# SCH_ESP32-LSHT-M-H-Project-Folder_2024-0.net
KiCad netlist of a schematic drawn in EasyEDA
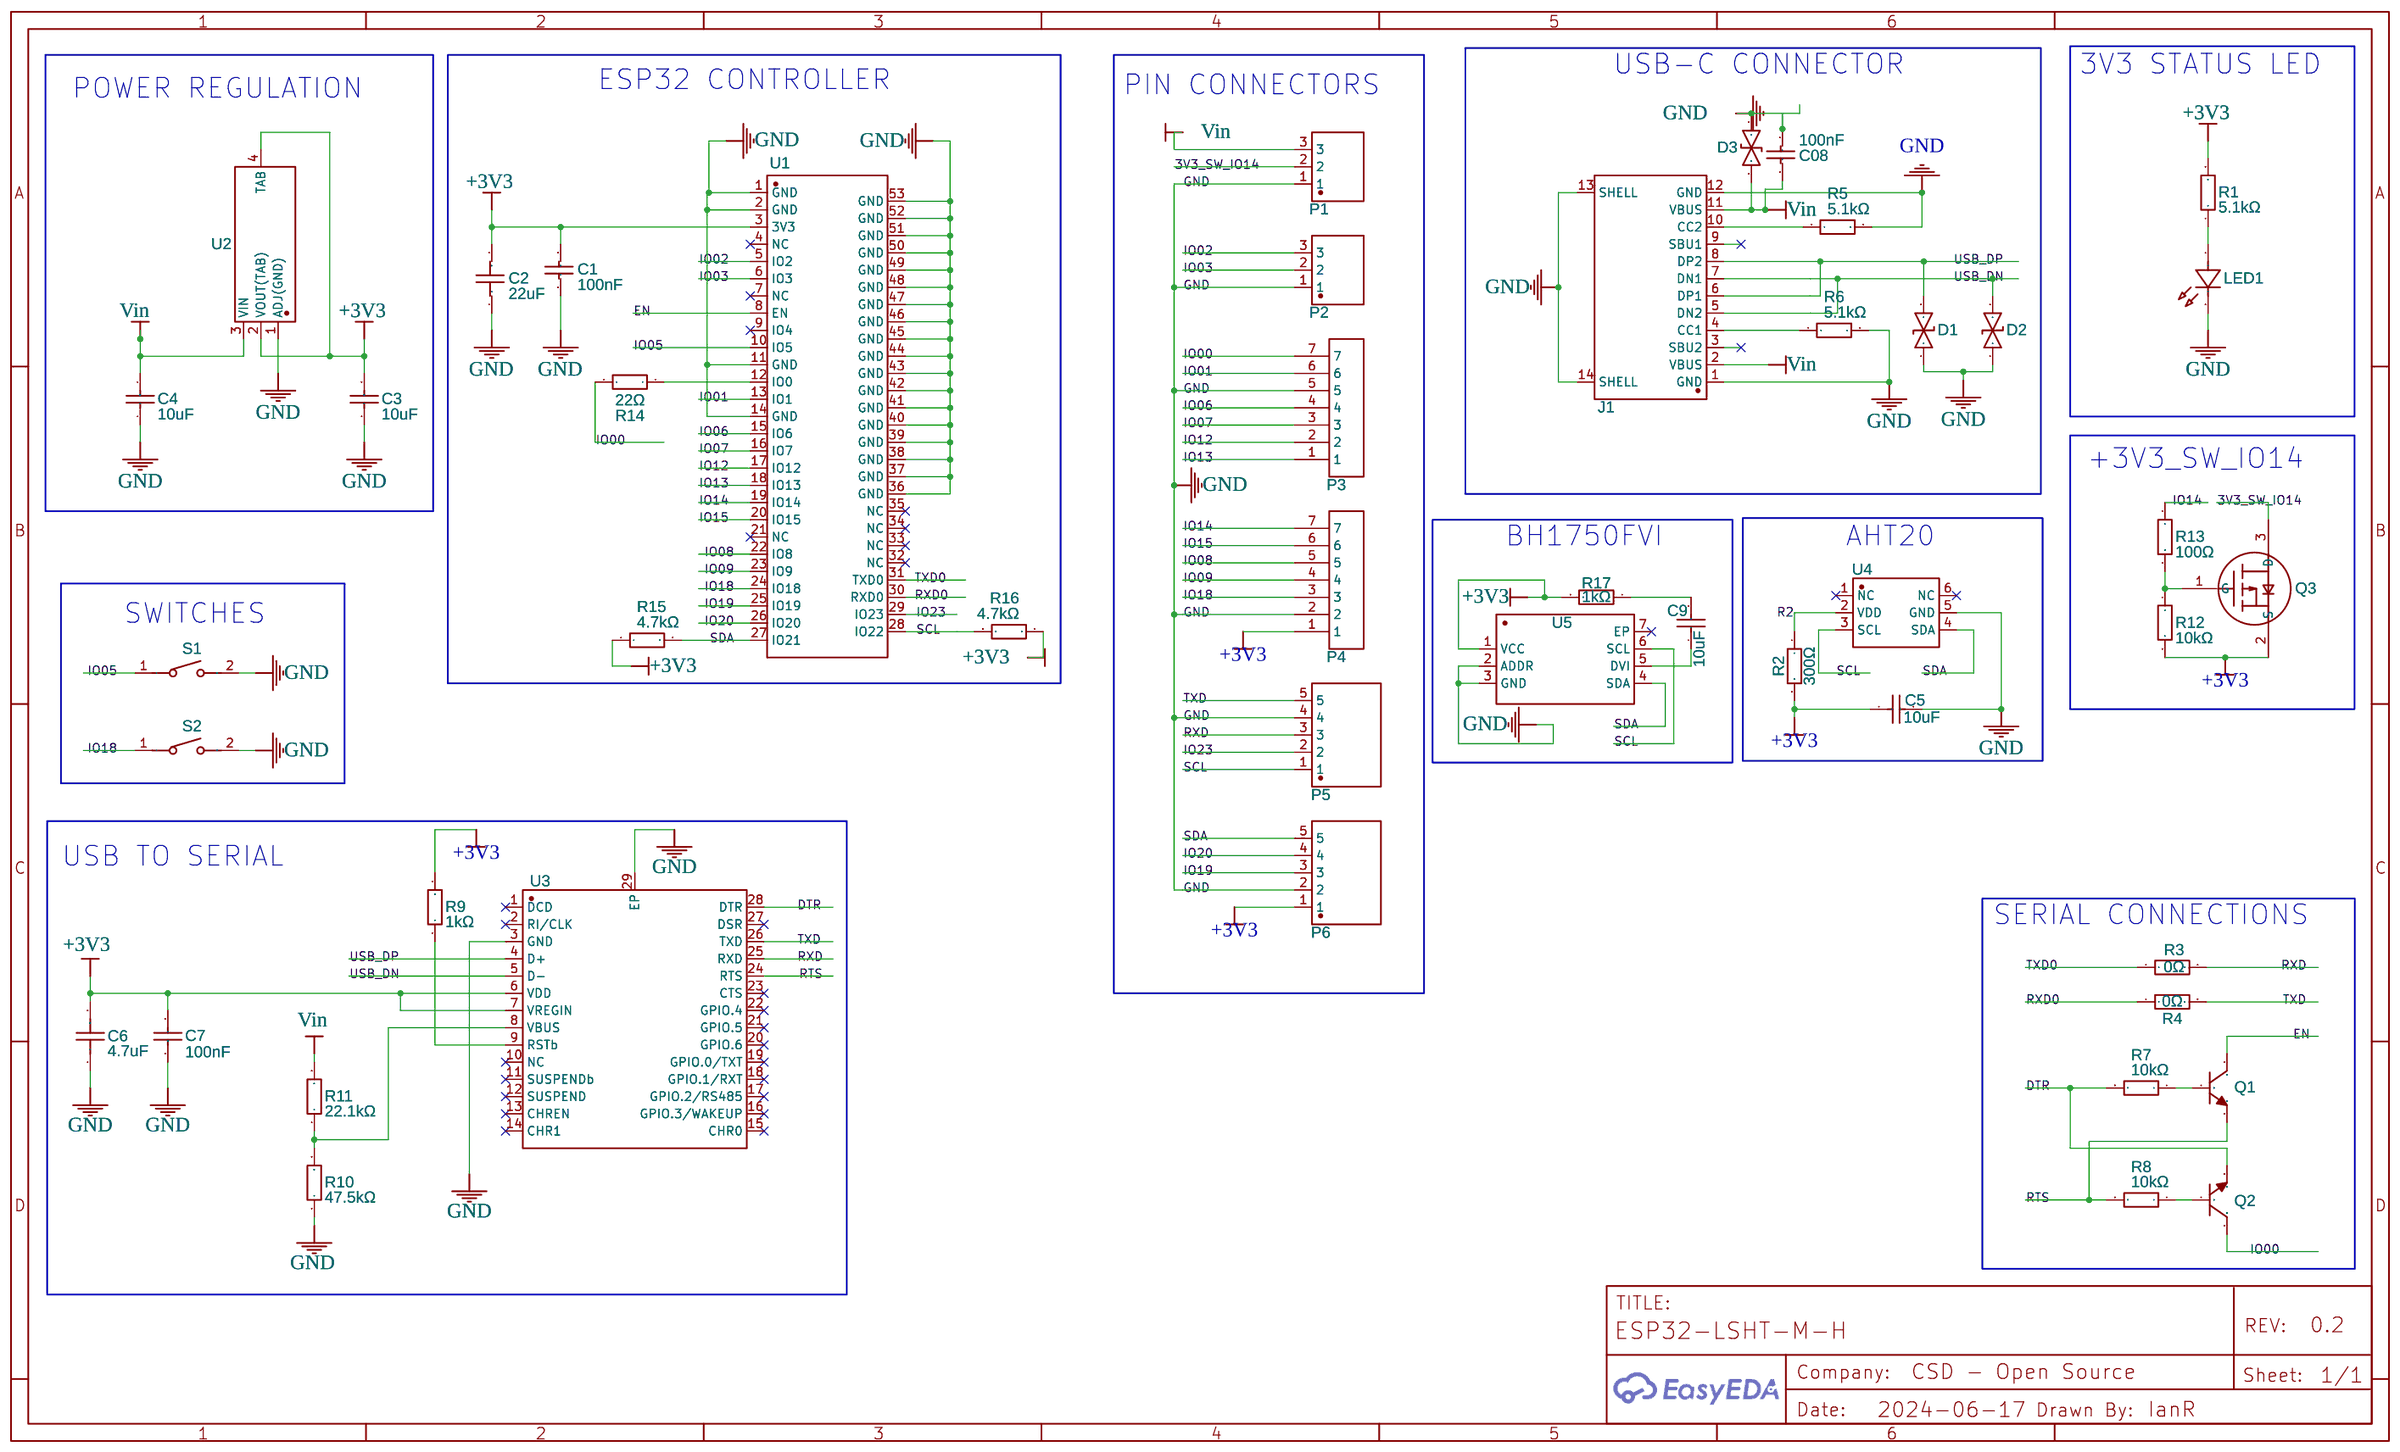
[diagram p0: schematic sheet]

(export (version "E")
  (design (tool "Eeschema 10.0.6"))
  (components
    (comp (ref "C1")
      (value "100nF")
      (fields
        (field (name "Manufacturer Part") "CL05B104KO5NNNC")
        (field (name "Manufacturer") "SAMSUNG(三星)")
      )
      (libsource (lib "") (part "CL05B104KO5NNNC"))
    )
    (comp (ref "C2")
      (value "22uF")
      (fields
        (field (name "Manufacturer Part") "GRM158R61A226ME15D")
        (field (name "Manufacturer") "muRata(村田)")
      )
      (libsource (lib "") (part "GRM158R61A226ME15D"))
    )
    (comp (ref "C3")
      (value "10uF")
      (fields
        (field (name "Manufacturer Part") "CL05A106MQ5NUNC")
        (field (name "Manufacturer") "SAMSUNG(三星)")
      )
      (libsource (lib "") (part "CL05A106MQ5NUNC_1"))
    )
    (comp (ref "C4")
      (value "10uF")
      (fields
        (field (name "Manufacturer Part") "CL05A106MQ5NUNC")
        (field (name "Manufacturer") "SAMSUNG(三星)")
      )
      (libsource (lib "") (part "CL05A106MQ5NUNC_1"))
    )
    (comp (ref "C5")
      (value "10uF")
      (fields
        (field (name "Manufacturer Part") "CL05A106MQ5NUNC")
        (field (name "Manufacturer") "SAMSUNG(三星)")
      )
      (libsource (lib "") (part "CL05A106MQ5NUNC"))
    )
    (comp (ref "C6")
      (value "4.7uF")
      (fields
        (field (name "Manufacturer Part") "CL05A475KP5NRNC")
        (field (name "Manufacturer") "SAMSUNG(三星)")
      )
      (libsource (lib "") (part "CL05A475KP5NRNC"))
    )
    (comp (ref "C7")
      (value "100nF")
      (fields
        (field (name "Manufacturer Part") "CL05B104KO5NNNC")
        (field (name "Manufacturer") "SAMSUNG(三星)")
      )
      (libsource (lib "") (part "CL05B104KO5NNNC_2"))
    )
    (comp (ref "C08")
      (value "100nF")
      (fields
        (field (name "Manufacturer Part") "CL05B104KO5NNNC")
        (field (name "Manufacturer") "SAMSUNG(三星)")
      )
      (libsource (lib "") (part "CL05B104KO5NNNC_1"))
    )
    (comp (ref "C9")
      (value "10uF")
      (fields
        (field (name "Manufacturer Part") "CL05A106MQ5NUNC")
        (field (name "Manufacturer") "SAMSUNG(三星)")
      )
      (libsource (lib "") (part "CL05A106MQ5NUNC_1"))
    )
    (comp (ref "D1")
      (value "LESD5D5.0CT1G_C5246195")
      (fields
        (field (name "Manufacturer Part") "LESD5D5.0CT1G")
        (field (name "Manufacturer") "Leiditech(雷卯电子)")
      )
      (libsource (lib "") (part "LESD5D5.0CT1G_C5246195_1"))
    )
    (comp (ref "D2")
      (value "LESD5D5.0CT1G_C5246195")
      (fields
        (field (name "Manufacturer Part") "LESD5D5.0CT1G")
        (field (name "Manufacturer") "Leiditech(雷卯电子)")
      )
      (libsource (lib "") (part "LESD5D5.0CT1G_C5246195_1"))
    )
    (comp (ref "D3")
      (value "LESD5D5.0CT1G_C5246195")
      (fields
        (field (name "Manufacturer Part") "LESD5D5.0CT1G")
        (field (name "Manufacturer") "Leiditech(雷卯电子)")
      )
      (libsource (lib "") (part "LESD5D5.0CT1G_C5246195"))
    )
    (comp (ref "J1")
      (value "TYPE-C 16PIN 2MD(073)")
      (fields (field (name "Manufacturer") "SHOU HAN(首韩)"))
      (libsource (lib "") (part "TYPE-C 16PIN 2MD(073)"))
    )
    (comp (ref "LED1")
      (value "XL-1005SURC")
      (fields (field (name "Manufacturer") "XINGLIGHT(成兴光)"))
      (libsource (lib "") (part "XL-1005SURC"))
    )
    (comp (ref "P1")
      (value "B3B-ZR-(LF)(SN)")
      (fields (field (name "Manufacturer Part") "B3B-ZR(LF)(SN)") (field (name "Manufacturer") "JST"))
      (libsource (lib "") (part "B3B-ZR-(LF)(SN)"))
    )
    (comp (ref "P2")
      (value "B3B-ZR-(LF)(SN)")
      (fields (field (name "Manufacturer Part") "B3B-ZR(LF)(SN)") (field (name "Manufacturer") "JST"))
      (libsource (lib "") (part "B3B-ZR-(LF)(SN)"))
    )
    (comp (ref "P3")
      (value "B7B-ZR (LF)(SN)")
      (fields (field (name "Manufacturer Part") "B7B-ZR(LF)(SN)") (field (name "Manufacturer") "JST"))
      (libsource (lib "") (part "B7B-ZR (LF)(SN)"))
    )
    (comp (ref "P4")
      (value "B7B-ZR (LF)(SN)")
      (fields (field (name "Manufacturer Part") "B7B-ZR(LF)(SN)") (field (name "Manufacturer") "JST"))
      (libsource (lib "") (part "B7B-ZR (LF)(SN)"))
    )
    (comp (ref "P5")
      (value "B5B-ZR-(LF)(SN)")
      (fields (field (name "Manufacturer Part") "B5B-ZR(LF)(SN)") (field (name "Manufacturer") "JST"))
      (libsource (lib "") (part "B5B-ZR-(LF)(SN)"))
    )
    (comp (ref "P6")
      (value "B5B-ZR-(LF)(SN)")
      (fields (field (name "Manufacturer Part") "B5B-ZR(LF)(SN)") (field (name "Manufacturer") "JST"))
      (libsource (lib "") (part "B5B-ZR-(LF)(SN)"))
    )
    (comp (ref "Q1")
      (value "SS8050-G")
      (fields (field (name "Manufacturer") "CJ(江苏长电/长晶)"))
      (libsource (lib "") (part "SS8050-G_1"))
    )
    (comp (ref "Q2")
      (value "SS8050-G")
      (fields (field (name "Manufacturer") "CJ(江苏长电/长晶)"))
      (libsource (lib "") (part "SS8050-G"))
    )
    (comp (ref "Q3")
      (value "SI2333DS-T1-E3")
      (fields (field (name "Manufacturer") "VISHAY(威世)"))
      (libsource (lib "") (part "SI2333DS-T1-E3"))
    )
    (comp (ref "R1")
      (value "5.1kΩ")
      (fields
        (field (name "Manufacturer Part") "0402WGF5101TCE")
        (field (name "Manufacturer") "UNI-ROYAL(厚声)")
      )
      (libsource (lib "") (part "0402WGF5101TCE_1"))
    )
    (comp (ref "R2")
      (value "300Ω")
      (fields (field (name "Manufacturer Part") "RC0402FR-07300RL") (field (name "Manufacturer") "YAGEO(国巨)"))
      (libsource (lib "") (part "RC0402FR-07300RL"))
    )
    (comp (ref "R3")
      (value "0Ω")
      (fields
        (field (name "Manufacturer Part") "0402WGF0000TCE")
        (field (name "Manufacturer") "UNI-ROYAL(厚声)")
      )
      (libsource (lib "") (part "0402WGF0000TCE"))
    )
    (comp (ref "R4")
      (value "0Ω")
      (fields
        (field (name "Manufacturer Part") "0402WGF0000TCE")
        (field (name "Manufacturer") "UNI-ROYAL(厚声)")
      )
      (libsource (lib "") (part "0402WGF0000TCE"))
    )
    (comp (ref "R5")
      (value "5.1kΩ")
      (fields
        (field (name "Manufacturer Part") "0402WGF5101TCE")
        (field (name "Manufacturer") "UNI-ROYAL(厚声)")
      )
      (libsource (lib "") (part "0402WGF5101TCE"))
    )
    (comp (ref "R6")
      (value "5.1kΩ")
      (fields
        (field (name "Manufacturer Part") "0402WGF5101TCE")
        (field (name "Manufacturer") "UNI-ROYAL(厚声)")
      )
      (libsource (lib "") (part "0402WGF5101TCE"))
    )
    (comp (ref "R7")
      (value "10kΩ")
      (fields
        (field (name "Manufacturer Part") "0402WGF1002TCE")
        (field (name "Manufacturer") "UNI-ROYAL(厚声)")
      )
      (libsource (lib "") (part "0402WGF1002TCE"))
    )
    (comp (ref "R8")
      (value "10kΩ")
      (fields
        (field (name "Manufacturer Part") "0402WGF1002TCE")
        (field (name "Manufacturer") "UNI-ROYAL(厚声)")
      )
      (libsource (lib "") (part "0402WGF1002TCE"))
    )
    (comp (ref "R9")
      (value "1kΩ")
      (fields
        (field (name "Manufacturer Part") "0402WGF1001TCE")
        (field (name "Manufacturer") "UNI-ROYAL(厚声)")
      )
      (libsource (lib "") (part "0402WGF1001TCE_1"))
    )
    (comp (ref "R10")
      (value "47.5kΩ")
      (fields
        (field (name "Manufacturer Part") "0402WGF4752TCE")
        (field (name "Manufacturer") "UNI-ROYAL(厚声)")
      )
      (libsource (lib "") (part "0402WGF4752TCE"))
    )
    (comp (ref "R11")
      (value "22.1kΩ")
      (fields
        (field (name "Manufacturer Part") "0402WGF2212TCE")
        (field (name "Manufacturer") "UNI-ROYAL(厚声)")
      )
      (libsource (lib "") (part "0402WGF2212TCE"))
    )
    (comp (ref "R12")
      (value "10kΩ")
      (fields
        (field (name "Manufacturer Part") "0402WGF1002TCE")
        (field (name "Manufacturer") "UNI-ROYAL(厚声)")
      )
      (libsource (lib "") (part "0402WGF1002TCE_1"))
    )
    (comp (ref "R13")
      (value "100Ω")
      (fields (field (name "Manufacturer Part") "RC0402FR-07100RL") (field (name "Manufacturer") "YAGEO(国巨)"))
      (libsource (lib "") (part "RC0402FR-07100RL"))
    )
    (comp (ref "R14")
      (value "22Ω")
      (fields
        (field (name "Manufacturer Part") "0402WGF220JTCE")
        (field (name "Manufacturer") "UNI-ROYAL(厚声)")
      )
      (libsource (lib "") (part "0402WGF220JTCE"))
    )
    (comp (ref "R15")
      (value "4.7kΩ")
      (fields
        (field (name "Manufacturer Part") "0402WGF4701TCE")
        (field (name "Manufacturer") "UNI-ROYAL(厚声)")
      )
      (libsource (lib "") (part "0402WGF4701TCE_1"))
    )
    (comp (ref "R16")
      (value "4.7kΩ")
      (fields
        (field (name "Manufacturer Part") "0402WGF4701TCE")
        (field (name "Manufacturer") "UNI-ROYAL(厚声)")
      )
      (libsource (lib "") (part "0402WGF4701TCE"))
    )
    (comp (ref "R17")
      (value "1kΩ")
      (fields
        (field (name "Manufacturer Part") "0402WGF1001TCE")
        (field (name "Manufacturer") "UNI-ROYAL(厚声)")
      )
      (libsource (lib "") (part "0402WGF1001TCE"))
    )
    (comp (ref "S1")
      (value "TS-1088-AR02016")
      (fields (field (name "Manufacturer") "XUNPU(讯普)"))
      (libsource (lib "") (part "TS-1088-AR02016"))
    )
    (comp (ref "S2")
      (value "TS-1088-AR02016")
      (fields (field (name "Manufacturer") "XUNPU(讯普)"))
      (libsource (lib "") (part "TS-1088-AR02016"))
    )
    (comp (ref "U1")
      (value "ESP32-C6-MINI-1-N4")
      (fields (field (name "Manufacturer") "ESPRESSIF(乐鑫)"))
      (libsource (lib "") (part "ESP32-C6-MINI-1-N4"))
    )
    (comp (ref "U2")
      (value "AMS1117-3.3_C347222")
      (fields (field (name "Manufacturer Part") "AMS1117-3.3") (field (name "Manufacturer") "UMW(友台半导体)"))
      (libsource (lib "") (part "AMS1117-3.3_C347222"))
    )
    (comp (ref "U3")
      (value "CP2102N-A02-GQFN28R")
      (fields (field (name "Manufacturer") "SKYWORKS/SILICON LABS(芯科)"))
      (libsource (lib "") (part "CP2102N-A02-GQFN28R"))
    )
    (comp (ref "U4")
      (value "AHT20_C2757850")
      (fields (field (name "Manufacturer Part") "AHT20") (field (name "Manufacturer") "广州奥松"))
      (libsource (lib "") (part "AHT20_C2757850"))
    )
    (comp (ref "U5")
      (value "BH1750FVI-TR")
      (fields (field (name "Manufacturer") "ROHM(罗姆)"))
      (libsource (lib "") (part "BH1750FVI-TR"))
    )
  )
  (nets
    (net (code "1") (name "+3V3") (class "Default")
      (node (ref "C1") (pin "2") (pinfunction "2_2") (pintype "input"))
      (node (ref "C2") (pin "2") (pinfunction "2_2") (pintype "unspecified"))
      (node (ref "C3") (pin "2") (pinfunction "2_2") (pintype "input"))
      (node (ref "C5") (pin "1") (pinfunction "1_1") (pintype "input"))
      (node (ref "C6") (pin "2") (pinfunction "2_2") (pintype "unspecified"))
      (node (ref "C7") (pin "2") (pinfunction "2_2") (pintype "input"))
      (node (ref "P4") (pin "1") (pinfunction "1_1") (pintype "unspecified"))
      (node (ref "P6") (pin "1") (pinfunction "1_1") (pintype "unspecified"))
      (node (ref "Q3") (pin "2") (pinfunction "S_2") (pintype "unspecified"))
      (node (ref "R1") (pin "2") (pinfunction "2_2") (pintype "input"))
      (node (ref "R12") (pin "2") (pinfunction "2_2") (pintype "input"))
      (node (ref "R15") (pin "1") (pinfunction "1_1") (pintype "input"))
      (node (ref "R16") (pin "1") (pinfunction "1_1") (pintype "input"))
      (node (ref "R17") (pin "2") (pinfunction "2_2") (pintype "input"))
      (node (ref "R2") (pin "2") (pinfunction "2_2") (pintype "input"))
      (node (ref "R9") (pin "2") (pinfunction "2_2") (pintype "input"))
      (node (ref "U1") (pin "3") (pinfunction "3V3_3") (pintype "unspecified"))
      (node (ref "U2") (pin "2") (pinfunction "VOUT(TAB)_2") (pintype "unspecified"))
      (node (ref "U2") (pin "4") (pinfunction "TAB_4") (pintype "unspecified"))
      (node (ref "U3") (pin "6") (pinfunction "VDD_6") (pintype "unspecified"))
      (node (ref "U3") (pin "7") (pinfunction "VREGIN_7") (pintype "unspecified"))
      (node (ref "U5") (pin "1") (pinfunction "VCC_1") (pintype "unspecified"))
    )
    (net (code "2") (name "/3V3_SW_IO14") (class "Default")
      (node (ref "P1") (pin "2") (pinfunction "2_2") (pintype "unspecified"))
      (node (ref "Q3") (pin "3") (pinfunction "D_3") (pintype "unspecified"))
    )
    (net (code "3") (name "/DTR") (class "Default")
      (node (ref "Q2") (pin "2") (pinfunction "E_2") (pintype "input"))
      (node (ref "R7") (pin "2") (pinfunction "2_2") (pintype "input"))
      (node (ref "U3") (pin "28") (pinfunction "DTR_28") (pintype "unspecified"))
    )
    (net (code "4") (name "/EN") (class "Default")
      (node (ref "Q1") (pin "3") (pinfunction "C_3") (pintype "input"))
      (node (ref "U1") (pin "8") (pinfunction "EN_8") (pintype "unspecified"))
    )
    (net (code "5") (name "/IO00") (class "Default")
      (node (ref "P3") (pin "7") (pinfunction "7_7") (pintype "unspecified"))
      (node (ref "Q2") (pin "3") (pinfunction "C_3") (pintype "input"))
      (node (ref "R14") (pin "2") (pinfunction "2_2") (pintype "input"))
    )
    (net (code "6") (name "/IO01") (class "Default")
      (node (ref "P3") (pin "6") (pinfunction "6_6") (pintype "unspecified"))
      (node (ref "U1") (pin "13") (pinfunction "IO1_13") (pintype "unspecified"))
    )
    (net (code "7") (name "/IO02") (class "Default")
      (node (ref "P2") (pin "3") (pinfunction "3_3") (pintype "unspecified"))
      (node (ref "U1") (pin "5") (pinfunction "IO2_5") (pintype "unspecified"))
    )
    (net (code "8") (name "/IO03") (class "Default")
      (node (ref "P2") (pin "2") (pinfunction "2_2") (pintype "unspecified"))
      (node (ref "U1") (pin "6") (pinfunction "IO3_6") (pintype "unspecified"))
    )
    (net (code "9") (name "/IO05") (class "Default")
      (node (ref "S1") (pin "1") (pinfunction "1_1") (pintype "unspecified"))
      (node (ref "U1") (pin "10") (pinfunction "IO5_10") (pintype "unspecified"))
    )
    (net (code "10") (name "/IO06") (class "Default")
      (node (ref "P3") (pin "4") (pinfunction "4_4") (pintype "unspecified"))
      (node (ref "U1") (pin "15") (pinfunction "IO6_15") (pintype "unspecified"))
    )
    (net (code "11") (name "/IO07") (class "Default")
      (node (ref "P3") (pin "3") (pinfunction "3_3") (pintype "unspecified"))
      (node (ref "U1") (pin "16") (pinfunction "IO7_16") (pintype "unspecified"))
    )
    (net (code "12") (name "/IO08") (class "Default")
      (node (ref "P4") (pin "5") (pinfunction "5_5") (pintype "unspecified"))
      (node (ref "U1") (pin "22") (pinfunction "IO8_22") (pintype "unspecified"))
    )
    (net (code "13") (name "/IO09") (class "Default")
      (node (ref "P4") (pin "4") (pinfunction "4_4") (pintype "unspecified"))
      (node (ref "U1") (pin "23") (pinfunction "IO9_23") (pintype "unspecified"))
    )
    (net (code "14") (name "/IO12") (class "Default")
      (node (ref "P3") (pin "2") (pinfunction "2_2") (pintype "unspecified"))
      (node (ref "U1") (pin "17") (pinfunction "IO12_17") (pintype "unspecified"))
    )
    (net (code "15") (name "/IO13") (class "Default")
      (node (ref "P3") (pin "1") (pinfunction "1_1") (pintype "unspecified"))
      (node (ref "U1") (pin "18") (pinfunction "IO13_18") (pintype "unspecified"))
    )
    (net (code "16") (name "/IO14") (class "Default")
      (node (ref "P4") (pin "7") (pinfunction "7_7") (pintype "unspecified"))
      (node (ref "R13") (pin "1") (pinfunction "1_1") (pintype "input"))
      (node (ref "U1") (pin "19") (pinfunction "IO14_19") (pintype "unspecified"))
    )
    (net (code "17") (name "/IO15") (class "Default")
      (node (ref "P4") (pin "6") (pinfunction "6_6") (pintype "unspecified"))
      (node (ref "U1") (pin "20") (pinfunction "IO15_20") (pintype "unspecified"))
    )
    (net (code "18") (name "/IO18") (class "Default")
      (node (ref "P4") (pin "3") (pinfunction "3_3") (pintype "unspecified"))
      (node (ref "S2") (pin "1") (pinfunction "1_1") (pintype "unspecified"))
      (node (ref "U1") (pin "24") (pinfunction "IO18_24") (pintype "unspecified"))
    )
    (net (code "19") (name "/IO19") (class "Default")
      (node (ref "P6") (pin "3") (pinfunction "3_3") (pintype "unspecified"))
      (node (ref "U1") (pin "25") (pinfunction "IO19_25") (pintype "unspecified"))
    )
    (net (code "20") (name "/IO20") (class "Default")
      (node (ref "P6") (pin "4") (pinfunction "4_4") (pintype "unspecified"))
      (node (ref "U1") (pin "26") (pinfunction "IO20_26") (pintype "unspecified"))
    )
    (net (code "21") (name "/IO23") (class "Default")
      (node (ref "P5") (pin "2") (pinfunction "2_2") (pintype "unspecified"))
      (node (ref "U1") (pin "29") (pinfunction "IO23_29") (pintype "unspecified"))
    )
    (net (code "22") (name "/R2") (class "Default")
      (node (ref "R2") (pin "1") (pinfunction "1_1") (pintype "input"))
      (node (ref "U4") (pin "2") (pinfunction "VDD_2") (pintype "unspecified"))
    )
    (net (code "23") (name "/RTS") (class "Default")
      (node (ref "Q1") (pin "2") (pinfunction "E_2") (pintype "input"))
      (node (ref "R8") (pin "2") (pinfunction "2_2") (pintype "input"))
      (node (ref "U3") (pin "24") (pinfunction "RTS_24") (pintype "unspecified"))
    )
    (net (code "24") (name "/RXD") (class "Default")
      (node (ref "P5") (pin "3") (pinfunction "3_3") (pintype "unspecified"))
      (node (ref "R3") (pin "2") (pinfunction "2_2") (pintype "input"))
      (node (ref "U3") (pin "25") (pinfunction "RXD_25") (pintype "unspecified"))
    )
    (net (code "25") (name "/RXD0") (class "Default")
      (node (ref "R4") (pin "1") (pinfunction "1_1") (pintype "input"))
      (node (ref "U1") (pin "30") (pinfunction "RXD0_30") (pintype "unspecified"))
    )
    (net (code "26") (name "/SCL") (class "Default")
      (node (ref "P5") (pin "1") (pinfunction "1_1") (pintype "unspecified"))
      (node (ref "R16") (pin "2") (pinfunction "2_2") (pintype "input"))
      (node (ref "U1") (pin "28") (pinfunction "IO22_28") (pintype "unspecified"))
      (node (ref "U4") (pin "3") (pinfunction "SCL_3") (pintype "unspecified"))
      (node (ref "U5") (pin "6") (pinfunction "SCL_6") (pintype "unspecified"))
    )
    (net (code "27") (name "/SDA") (class "Default")
      (node (ref "P6") (pin "5") (pinfunction "5_5") (pintype "unspecified"))
      (node (ref "R15") (pin "2") (pinfunction "2_2") (pintype "input"))
      (node (ref "U1") (pin "27") (pinfunction "IO21_27") (pintype "unspecified"))
      (node (ref "U4") (pin "4") (pinfunction "SDA_4") (pintype "unspecified"))
      (node (ref "U5") (pin "4") (pinfunction "SDA_4") (pintype "unspecified"))
    )
    (net (code "28") (name "/TXD") (class "Default")
      (node (ref "P5") (pin "5") (pinfunction "5_5") (pintype "unspecified"))
      (node (ref "R4") (pin "2") (pinfunction "2_2") (pintype "input"))
      (node (ref "U3") (pin "26") (pinfunction "TXD_26") (pintype "unspecified"))
    )
    (net (code "29") (name "/TXD0") (class "Default")
      (node (ref "R3") (pin "1") (pinfunction "1_1") (pintype "input"))
      (node (ref "U1") (pin "31") (pinfunction "TXD0_31") (pintype "unspecified"))
    )
    (net (code "30") (name "/USB_DN") (class "Default")
      (node (ref "D2") (pin "2") (pinfunction "2_2") (pintype "unspecified"))
      (node (ref "J1") (pin "5") (pinfunction "DN2_5") (pintype "unspecified"))
      (node (ref "J1") (pin "7") (pinfunction "DN1_7") (pintype "unspecified"))
      (node (ref "U3") (pin "5") (pinfunction "D-_5") (pintype "unspecified"))
    )
    (net (code "31") (name "/USB_DP") (class "Default")
      (node (ref "D1") (pin "2") (pinfunction "2_2") (pintype "unspecified"))
      (node (ref "J1") (pin "6") (pinfunction "DP1_6") (pintype "unspecified"))
      (node (ref "J1") (pin "8") (pinfunction "DP2_8") (pintype "unspecified"))
      (node (ref "U3") (pin "4") (pinfunction "D+_4") (pintype "unspecified"))
    )
    (net (code "32") (name "GND") (class "Default")
      (node (ref "C08") (pin "1") (pinfunction "1_1") (pintype "input"))
      (node (ref "C1") (pin "1") (pinfunction "1_1") (pintype "input"))
      (node (ref "C2") (pin "1") (pinfunction "1_1") (pintype "unspecified"))
      (node (ref "C3") (pin "1") (pinfunction "1_1") (pintype "input"))
      (node (ref "C4") (pin "1") (pinfunction "1_1") (pintype "input"))
      (node (ref "C5") (pin "2") (pinfunction "2_2") (pintype "input"))
      (node (ref "C6") (pin "1") (pinfunction "1_1") (pintype "unspecified"))
      (node (ref "C7") (pin "1") (pinfunction "1_1") (pintype "input"))
      (node (ref "D1") (pin "1") (pinfunction "1_1") (pintype "unspecified"))
      (node (ref "D2") (pin "1") (pinfunction "1_1") (pintype "unspecified"))
      (node (ref "D3") (pin "1") (pinfunction "1_1") (pintype "unspecified"))
      (node (ref "J1") (pin "1") (pinfunction "GND_1") (pintype "unspecified"))
      (node (ref "J1") (pin "12") (pinfunction "GND_12") (pintype "unspecified"))
      (node (ref "J1") (pin "13") (pinfunction "SHELL_13") (pintype "unspecified"))
      (node (ref "J1") (pin "14") (pinfunction "SHELL_14") (pintype "unspecified"))
      (node (ref "LED1") (pin "2") (pinfunction "A_2") (pintype "unspecified"))
      (node (ref "P1") (pin "1") (pinfunction "1_1") (pintype "unspecified"))
      (node (ref "P2") (pin "1") (pinfunction "1_1") (pintype "unspecified"))
      (node (ref "P3") (pin "5") (pinfunction "5_5") (pintype "unspecified"))
      (node (ref "P4") (pin "2") (pinfunction "2_2") (pintype "unspecified"))
      (node (ref "P5") (pin "4") (pinfunction "4_4") (pintype "unspecified"))
      (node (ref "P6") (pin "2") (pinfunction "2_2") (pintype "unspecified"))
      (node (ref "R10") (pin "1") (pinfunction "1_1") (pintype "input"))
      (node (ref "R5") (pin "2") (pinfunction "2_2") (pintype "input"))
      (node (ref "R6") (pin "2") (pinfunction "2_2") (pintype "input"))
      (node (ref "S1") (pin "2") (pinfunction "2_2") (pintype "unspecified"))
      (node (ref "S2") (pin "2") (pinfunction "2_2") (pintype "unspecified"))
      (node (ref "U1") (pin "1") (pinfunction "GND_1") (pintype "unspecified"))
      (node (ref "U1") (pin "11") (pinfunction "GND_11") (pintype "unspecified"))
      (node (ref "U1") (pin "14") (pinfunction "GND_14") (pintype "unspecified"))
      (node (ref "U1") (pin "2") (pinfunction "GND_2") (pintype "unspecified"))
      (node (ref "U1") (pin "36") (pinfunction "GND_36") (pintype "unspecified"))
      (node (ref "U1") (pin "37") (pinfunction "GND_37") (pintype "unspecified"))
      (node (ref "U1") (pin "38") (pinfunction "GND_38") (pintype "unspecified"))
      (node (ref "U1") (pin "39") (pinfunction "GND_39") (pintype "unspecified"))
      (node (ref "U1") (pin "40") (pinfunction "GND_40") (pintype "unspecified"))
      (node (ref "U1") (pin "41") (pinfunction "GND_41") (pintype "unspecified"))
      (node (ref "U1") (pin "42") (pinfunction "GND_42") (pintype "unspecified"))
      (node (ref "U1") (pin "43") (pinfunction "GND_43") (pintype "unspecified"))
      (node (ref "U1") (pin "44") (pinfunction "GND_44") (pintype "unspecified"))
      (node (ref "U1") (pin "45") (pinfunction "GND_45") (pintype "unspecified"))
      (node (ref "U1") (pin "46") (pinfunction "GND_46") (pintype "unspecified"))
      (node (ref "U1") (pin "47") (pinfunction "GND_47") (pintype "unspecified"))
      (node (ref "U1") (pin "48") (pinfunction "GND_48") (pintype "unspecified"))
      (node (ref "U1") (pin "49") (pinfunction "GND_49") (pintype "unspecified"))
      (node (ref "U1") (pin "50") (pinfunction "GND_50") (pintype "unspecified"))
      (node (ref "U1") (pin "51") (pinfunction "GND_51") (pintype "unspecified"))
      (node (ref "U1") (pin "52") (pinfunction "GND_52") (pintype "unspecified"))
      (node (ref "U1") (pin "53") (pinfunction "GND_53") (pintype "unspecified"))
      (node (ref "U2") (pin "1") (pinfunction "ADJ(GND)_1") (pintype "unspecified"))
      (node (ref "U3") (pin "29") (pinfunction "EP_29") (pintype "unspecified"))
      (node (ref "U3") (pin "3") (pinfunction "GND_3") (pintype "unspecified"))
      (node (ref "U4") (pin "5") (pinfunction "GND_5") (pintype "unspecified"))
      (node (ref "U5") (pin "2") (pinfunction "ADDR_2") (pintype "unspecified"))
      (node (ref "U5") (pin "3") (pinfunction "GND_3") (pintype "unspecified"))
    )
    (net (code "33") (name "Net-(C9-Pad2)") (class "Default")
      (node (ref "C9") (pin "2") (pinfunction "2_2") (pintype "input"))
      (node (ref "R17") (pin "1") (pinfunction "1_1") (pintype "input"))
    )
    (net (code "34") (name "Net-(J1-CC1)") (class "Default")
      (node (ref "J1") (pin "4") (pinfunction "CC1_4") (pintype "unspecified"))
      (node (ref "R6") (pin "1") (pinfunction "1_1") (pintype "input"))
    )
    (net (code "35") (name "Net-(J1-CC2)") (class "Default")
      (node (ref "J1") (pin "10") (pinfunction "CC2_10") (pintype "unspecified"))
      (node (ref "R5") (pin "1") (pinfunction "1_1") (pintype "input"))
    )
    (net (code "36") (name "Net-(LED1-K)") (class "Default")
      (node (ref "LED1") (pin "1") (pinfunction "K_1") (pintype "unspecified"))
      (node (ref "R1") (pin "1") (pinfunction "1_1") (pintype "input"))
    )
    (net (code "37") (name "Net-(Q1-B)") (class "Default")
      (node (ref "Q1") (pin "1") (pinfunction "B_1") (pintype "input"))
      (node (ref "R7") (pin "1") (pinfunction "1_1") (pintype "input"))
    )
    (net (code "38") (name "Net-(Q2-B)") (class "Default")
      (node (ref "Q2") (pin "1") (pinfunction "B_1") (pintype "input"))
      (node (ref "R8") (pin "1") (pinfunction "1_1") (pintype "input"))
    )
    (net (code "39") (name "Net-(Q3-G)") (class "Default")
      (node (ref "Q3") (pin "1") (pinfunction "G_1") (pintype "unspecified"))
      (node (ref "R12") (pin "1") (pinfunction "1_1") (pintype "input"))
      (node (ref "R13") (pin "2") (pinfunction "2_2") (pintype "input"))
    )
    (net (code "40") (name "Net-(U1-IO0)") (class "Default")
      (node (ref "R14") (pin "1") (pinfunction "1_1") (pintype "input"))
      (node (ref "U1") (pin "12") (pinfunction "IO0_12") (pintype "unspecified"))
    )
    (net (code "41") (name "Net-(U3-RSTb)") (class "Default")
      (node (ref "R9") (pin "1") (pinfunction "1_1") (pintype "input"))
      (node (ref "U3") (pin "9") (pinfunction "RSTb_9") (pintype "unspecified"))
    )
    (net (code "42") (name "Net-(U3-VBUS)") (class "Default")
      (node (ref "R10") (pin "2") (pinfunction "2_2") (pintype "input"))
      (node (ref "R11") (pin "1") (pinfunction "1_1") (pintype "input"))
      (node (ref "U3") (pin "8") (pinfunction "VBUS_8") (pintype "unspecified"))
    )
    (net (code "43") (name "Net-(U5-DVI)") (class "Default")
      (node (ref "C9") (pin "1") (pinfunction "1_1") (pintype "input"))
      (node (ref "U5") (pin "5") (pinfunction "DVI_5") (pintype "unspecified"))
    )
    (net (code "44") (name "Vin") (class "Default")
      (node (ref "C08") (pin "2") (pinfunction "2_2") (pintype "input"))
      (node (ref "C4") (pin "2") (pinfunction "2_2") (pintype "input"))
      (node (ref "D3") (pin "2") (pinfunction "2_2") (pintype "unspecified"))
      (node (ref "J1") (pin "11") (pinfunction "VBUS_11") (pintype "unspecified"))
      (node (ref "J1") (pin "2") (pinfunction "VBUS_2") (pintype "unspecified"))
      (node (ref "P1") (pin "3") (pinfunction "3_3") (pintype "unspecified"))
      (node (ref "R11") (pin "2") (pinfunction "2_2") (pintype "input"))
      (node (ref "U2") (pin "3") (pinfunction "VIN_3") (pintype "unspecified"))
    )
    (net (code "45") (name "unconnected-(J1-SBU1-Pad9)") (class "Default")
      (node (ref "J1") (pin "9") (pinfunction "SBU1_9") (pintype "unspecified+no_connect"))
    )
    (net (code "46") (name "unconnected-(J1-SBU2-Pad3)") (class "Default")
      (node (ref "J1") (pin "3") (pinfunction "SBU2_3") (pintype "unspecified+no_connect"))
    )
    (net (code "47") (name "unconnected-(U1-IO4-Pad9)") (class "Default")
      (node (ref "U1") (pin "9") (pinfunction "IO4_9") (pintype "unspecified+no_connect"))
    )
    (net (code "48") (name "unconnected-(U1-NC-Pad4)") (class "Default")
      (node (ref "U1") (pin "4") (pinfunction "NC_4") (pintype "unspecified+no_connect"))
    )
    (net (code "49") (name "unconnected-(U1-NC-Pad7)") (class "Default")
      (node (ref "U1") (pin "7") (pinfunction "NC_7") (pintype "unspecified+no_connect"))
    )
    (net (code "50") (name "unconnected-(U1-NC-Pad21)") (class "Default")
      (node (ref "U1") (pin "21") (pinfunction "NC_21") (pintype "unspecified+no_connect"))
    )
    (net (code "51") (name "unconnected-(U1-NC-Pad32)") (class "Default")
      (node (ref "U1") (pin "32") (pinfunction "NC_32") (pintype "unspecified+no_connect"))
    )
    (net (code "52") (name "unconnected-(U1-NC-Pad33)") (class "Default")
      (node (ref "U1") (pin "33") (pinfunction "NC_33") (pintype "unspecified+no_connect"))
    )
    (net (code "53") (name "unconnected-(U1-NC-Pad34)") (class "Default")
      (node (ref "U1") (pin "34") (pinfunction "NC_34") (pintype "unspecified+no_connect"))
    )
    (net (code "54") (name "unconnected-(U1-NC-Pad35)") (class "Default")
      (node (ref "U1") (pin "35") (pinfunction "NC_35") (pintype "unspecified+no_connect"))
    )
    (net (code "55") (name "unconnected-(U3-CHR0-Pad15)") (class "Default")
      (node (ref "U3") (pin "15") (pinfunction "CHR0_15") (pintype "unspecified+no_connect"))
    )
    (net (code "56") (name "unconnected-(U3-CHR1-Pad14)") (class "Default")
      (node (ref "U3") (pin "14") (pinfunction "CHR1_14") (pintype "unspecified+no_connect"))
    )
    (net (code "57") (name "unconnected-(U3-CHREN-Pad13)") (class "Default")
      (node (ref "U3") (pin "13") (pinfunction "CHREN_13") (pintype "unspecified+no_connect"))
    )
    (net (code "58") (name "unconnected-(U3-CTS-Pad23)") (class "Default")
      (node (ref "U3") (pin "23") (pinfunction "CTS_23") (pintype "unspecified+no_connect"))
    )
    (net (code "59") (name "unconnected-(U3-DCD-Pad1)") (class "Default")
      (node (ref "U3") (pin "1") (pinfunction "DCD_1") (pintype "unspecified+no_connect"))
    )
    (net (code "60") (name "unconnected-(U3-DSR-Pad27)") (class "Default")
      (node (ref "U3") (pin "27") (pinfunction "DSR_27") (pintype "unspecified+no_connect"))
    )
    (net (code "61") (name "unconnected-(U3-GPIO.0{slash}TXT-Pad19)") (class "Default")
      (node (ref "U3") (pin "19") (pinfunction "GPIO.0/TXT_19") (pintype "unspecified+no_connect"))
    )
    (net (code "62") (name "unconnected-(U3-GPIO.1{slash}RXT-Pad18)") (class "Default")
      (node (ref "U3") (pin "18") (pinfunction "GPIO.1/RXT_18") (pintype "unspecified+no_connect"))
    )
    (net (code "63") (name "unconnected-(U3-GPIO.2{slash}RS485-Pad17)") (class "Default")
      (node (ref "U3") (pin "17") (pinfunction "GPIO.2/RS485_17") (pintype "unspecified+no_connect"))
    )
    (net (code "64") (name "unconnected-(U3-GPIO.3{slash}WAKEUP-Pad16)") (class "Default")
      (node (ref "U3") (pin "16") (pinfunction "GPIO.3/WAKEUP_16") (pintype "unspecified+no_connect"))
    )
    (net (code "65") (name "unconnected-(U3-GPIO.4-Pad22)") (class "Default")
      (node (ref "U3") (pin "22") (pinfunction "GPIO.4_22") (pintype "unspecified+no_connect"))
    )
    (net (code "66") (name "unconnected-(U3-GPIO.5-Pad21)") (class "Default")
      (node (ref "U3") (pin "21") (pinfunction "GPIO.5_21") (pintype "unspecified+no_connect"))
    )
    (net (code "67") (name "unconnected-(U3-GPIO.6-Pad20)") (class "Default")
      (node (ref "U3") (pin "20") (pinfunction "GPIO.6_20") (pintype "unspecified+no_connect"))
    )
    (net (code "68") (name "unconnected-(U3-NC-Pad10)") (class "Default")
      (node (ref "U3") (pin "10") (pinfunction "NC_10") (pintype "unspecified+no_connect"))
    )
    (net (code "69") (name "unconnected-(U3-RI{slash}CLK-Pad2)") (class "Default")
      (node (ref "U3") (pin "2") (pinfunction "RI/CLK_2") (pintype "unspecified+no_connect"))
    )
    (net (code "70") (name "unconnected-(U3-SUSPEND-Pad12)") (class "Default")
      (node (ref "U3") (pin "12") (pinfunction "SUSPEND_12") (pintype "unspecified+no_connect"))
    )
    (net (code "71") (name "unconnected-(U3-SUSPENDb-Pad11)") (class "Default")
      (node (ref "U3") (pin "11") (pinfunction "SUSPENDb_11") (pintype "unspecified+no_connect"))
    )
    (net (code "72") (name "unconnected-(U4-NC-Pad1)") (class "Default")
      (node (ref "U4") (pin "1") (pinfunction "NC_1") (pintype "unspecified+no_connect"))
    )
    (net (code "73") (name "unconnected-(U4-NC-Pad6)") (class "Default")
      (node (ref "U4") (pin "6") (pinfunction "NC_6") (pintype "unspecified+no_connect"))
    )
    (net (code "74") (name "unconnected-(U5-EP-Pad7)") (class "Default")
      (node (ref "U5") (pin "7") (pinfunction "EP_7") (pintype "unspecified+no_connect"))
    )
  )
)
